# blink1mk3_005t5_5050.net
KiCad netlist of a schematic drawn in EAGLE
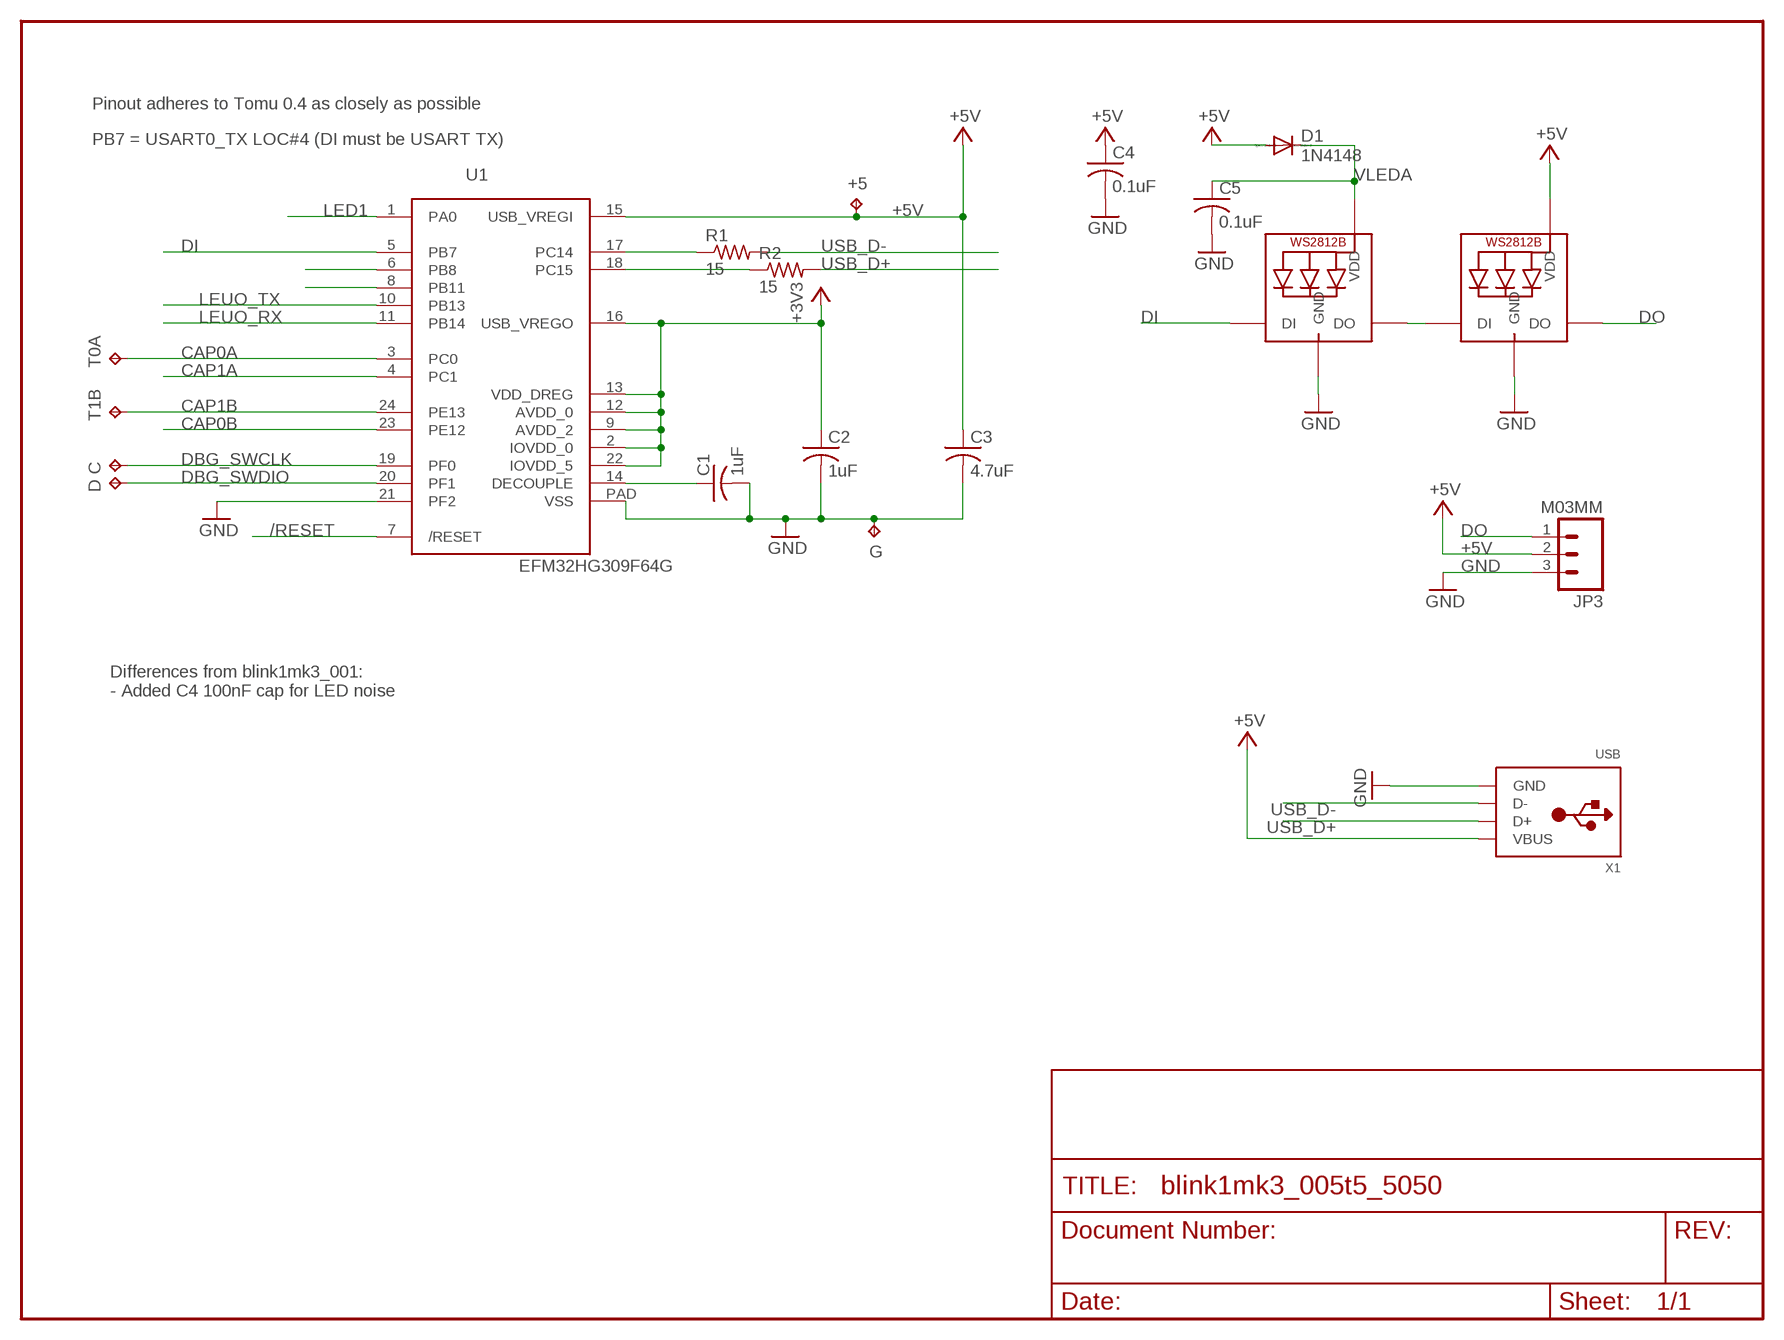
[diagram p0: schematic, sheet 1]

(export (version "E")
  (design (tool "Eeschema 10.0.6"))
  (components
    (comp (ref "+5")
      (value "TPTP10R")
      (footprint "eagle-import:TP10R")
      (libsource (lib "eagle-import") (part "TPTP10R"))
    )
    (comp (ref "C")
      (value "TPTP10R")
      (footprint "eagle-import:TP10R")
      (libsource (lib "eagle-import") (part "TPTP10R"))
    )
    (comp (ref "C1")
      (value "1uF")
      (footprint "eagle-import:C0402")
      (libsource (lib "eagle-import") (part "C-USC0402"))
    )
    (comp (ref "C2")
      (value "1uF")
      (footprint "eagle-import:C0402")
      (libsource (lib "eagle-import") (part "C-USC0402"))
    )
    (comp (ref "C3")
      (value "4.7uF")
      (footprint "eagle-import:C0402")
      (libsource (lib "eagle-import") (part "C-USC0402"))
    )
    (comp (ref "C4")
      (value "0.1uF")
      (footprint "eagle-import:C0402")
      (libsource (lib "eagle-import") (part "C-USC0402"))
    )
    (comp (ref "C5")
      (value "0.1uF")
      (footprint "eagle-import:C0402")
      (libsource (lib "eagle-import") (part "C-USC0402"))
    )
    (comp (ref "D")
      (value "TPTP10R")
      (footprint "eagle-import:TP10R")
      (libsource (lib "eagle-import") (part "TPTP10R"))
    )
    (comp (ref "D1")
      (value "1N4148")
      (footprint "eagle-import:SOD523")
      (libsource (lib "eagle-import") (part "DIODE-SOD523"))
    )
    (comp (ref "G")
      (value "TPTP10R")
      (footprint "eagle-import:TP10R")
      (libsource (lib "eagle-import") (part "TPTP10R"))
    )
    (comp (ref "JP3")
      (value "M03MM")
      (footprint "eagle-import:1X03-1.5MM")
      (libsource (lib "eagle-import") (part "M03MM"))
    )
    (comp (ref "LED1")
      (value "SK6812MINI")
      (footprint "eagle-import:WS2812B")
      (libsource (lib "eagle-import") (part "WS2812B5050"))
    )
    (comp (ref "LED2")
      (value "SK6812MINI")
      (footprint "eagle-import:WS2812B")
      (libsource (lib "eagle-import") (part "WS2812B5050"))
    )
    (comp (ref "R1")
      (value "15")
      (footprint "eagle-import:R0402")
      (libsource (lib "eagle-import") (part "R-US_R0402"))
    )
    (comp (ref "R2")
      (value "15")
      (footprint "eagle-import:R0402")
      (libsource (lib "eagle-import") (part "R-US_R0402"))
    )
    (comp (ref "T0A")
      (value "TPTP15R")
      (footprint "eagle-import:TP15R")
      (libsource (lib "eagle-import") (part "TPTP15R"))
    )
    (comp (ref "T1B")
      (value "TPTP15R")
      (footprint "eagle-import:TP15R")
      (libsource (lib "eagle-import") (part "TPTP15R"))
    )
    (comp (ref "U1")
      (value "EFM32HG309F64G")
      (footprint "eagle-import:QFN24PAD")
      (libsource (lib "eagle-import") (part "EFM32HG309F64G"))
    )
    (comp (ref "X1")
      (value "USB")
      (footprint "eagle-import:MOLEX-48037-1000")
      (libsource (lib "eagle-import") (part "USB"))
    )
  )
  (nets
    (net (code "1") (name "+3V3") (class "Default")
      (node (ref "C2") (pin "1") (pinfunction "1_1") (pintype "passive"))
      (node (ref "U1") (pin "12") (pinfunction "AVDD_0_12") (pintype "bidirectional"))
      (node (ref "U1") (pin "13") (pinfunction "VDD_DREG_13") (pintype "bidirectional"))
      (node (ref "U1") (pin "16") (pinfunction "USB_VREGO_16") (pintype "bidirectional"))
      (node (ref "U1") (pin "2") (pinfunction "IOVDD_0_2") (pintype "bidirectional"))
      (node (ref "U1") (pin "22") (pinfunction "IOVDD_5_22") (pintype "bidirectional"))
      (node (ref "U1") (pin "9") (pinfunction "AVDD_2_9") (pintype "bidirectional"))
    )
    (net (code "2") (name "+5V") (class "Default")
      (node (ref "+5") (pin "TP") (pinfunction "TP_TP") (pintype "input"))
      (node (ref "C3") (pin "1") (pinfunction "1_1") (pintype "passive"))
      (node (ref "C4") (pin "1") (pinfunction "1_1") (pintype "passive"))
      (node (ref "D1") (pin "A") (pinfunction "A_A") (pintype "passive"))
      (node (ref "JP3") (pin "2") (pinfunction "2_2") (pintype "passive"))
      (node (ref "LED2") (pin "1-VDD") (pinfunction "VDD_1-VDD") (pintype "power_in"))
      (node (ref "U1") (pin "15") (pinfunction "USB_VREGI_15") (pintype "bidirectional"))
      (node (ref "X1") (pin "1") (pinfunction "VBUS_1") (pintype "power_in"))
    )
    (net (code "3") (name "/CAP0A") (class "Default")
      (node (ref "T0A") (pin "TP") (pinfunction "TP_TP") (pintype "input"))
      (node (ref "U1") (pin "3") (pinfunction "PC0_3") (pintype "bidirectional"))
    )
    (net (code "4") (name "/CAP0B") (class "Default")
      (node (ref "U1") (pin "23") (pinfunction "PE12_23") (pintype "bidirectional"))
    )
    (net (code "5") (name "/CAP1A") (class "Default")
      (node (ref "U1") (pin "4") (pinfunction "PC1_4") (pintype "bidirectional"))
    )
    (net (code "6") (name "/CAP1B") (class "Default")
      (node (ref "T1B") (pin "TP") (pinfunction "TP_TP") (pintype "input"))
      (node (ref "U1") (pin "24") (pinfunction "PE13_24") (pintype "bidirectional"))
    )
    (net (code "7") (name "/DBG_SWCLK") (class "Default")
      (node (ref "C") (pin "TP") (pinfunction "TP_TP") (pintype "input"))
      (node (ref "U1") (pin "19") (pinfunction "PF0_19") (pintype "bidirectional"))
    )
    (net (code "8") (name "/DBG_SWDIO") (class "Default")
      (node (ref "D") (pin "TP") (pinfunction "TP_TP") (pintype "input"))
      (node (ref "U1") (pin "20") (pinfunction "PF1_20") (pintype "bidirectional"))
    )
    (net (code "9") (name "/DI") (class "Default")
      (node (ref "LED1") (pin "4-DIN") (pinfunction "DI_4-DIN") (pintype "input"))
      (node (ref "U1") (pin "5") (pinfunction "PB7_5") (pintype "bidirectional"))
    )
    (net (code "10") (name "/DO") (class "Default")
      (node (ref "JP3") (pin "1") (pinfunction "1_1") (pintype "passive"))
      (node (ref "LED2") (pin "2-DOUT") (pinfunction "DO_2-DOUT") (pintype "output"))
    )
    (net (code "11") (name "/LED1") (class "Default")
      (node (ref "U1") (pin "1") (pinfunction "PA0_1") (pintype "bidirectional"))
    )
    (net (code "12") (name "/LEUO_RX") (class "Default")
      (node (ref "U1") (pin "11") (pinfunction "PB14_11") (pintype "bidirectional"))
    )
    (net (code "13") (name "/LEUO_TX") (class "Default")
      (node (ref "U1") (pin "10") (pinfunction "PB13_10") (pintype "bidirectional"))
    )
    (net (code "14") (name "/USB_D+") (class "Default")
      (node (ref "R2") (pin "2") (pinfunction "2_2") (pintype "passive"))
      (node (ref "X1") (pin "3") (pinfunction "D+_3") (pintype "bidirectional"))
    )
    (net (code "15") (name "/USB_D-") (class "Default")
      (node (ref "R1") (pin "2") (pinfunction "2_2") (pintype "passive"))
      (node (ref "X1") (pin "2") (pinfunction "D-_2") (pintype "bidirectional"))
    )
    (net (code "16") (name "/VLEDA") (class "Default")
      (node (ref "C5") (pin "1") (pinfunction "1_1") (pintype "passive"))
      (node (ref "D1") (pin "C") (pinfunction "C_C") (pintype "passive"))
      (node (ref "LED1") (pin "1-VDD") (pinfunction "VDD_1-VDD") (pintype "power_in"))
    )
    (net (code "17") (name "/{slash}RESET") (class "Default")
      (node (ref "U1") (pin "7") (pinfunction "/RESET_7") (pintype "bidirectional"))
    )
    (net (code "18") (name "GND") (class "Default")
      (node (ref "C1") (pin "2") (pinfunction "2_2") (pintype "passive"))
      (node (ref "C2") (pin "2") (pinfunction "2_2") (pintype "passive"))
      (node (ref "C3") (pin "2") (pinfunction "2_2") (pintype "passive"))
      (node (ref "C4") (pin "2") (pinfunction "2_2") (pintype "passive"))
      (node (ref "C5") (pin "2") (pinfunction "2_2") (pintype "passive"))
      (node (ref "G") (pin "TP") (pinfunction "TP_TP") (pintype "input"))
      (node (ref "JP3") (pin "3") (pinfunction "3_3") (pintype "passive"))
      (node (ref "LED1") (pin "3-GND") (pinfunction "GND_3-GND") (pintype "power_in"))
      (node (ref "LED2") (pin "3-GND") (pinfunction "GND_3-GND") (pintype "power_in"))
      (node (ref "U1") (pin "21") (pinfunction "PF2_21") (pintype "bidirectional"))
      (node (ref "U1") (pin "PAD") (pinfunction "VSS_PAD") (pintype "bidirectional"))
      (node (ref "X1") (pin "4") (pinfunction "GND_4") (pintype "power_in"))
    )
    (net (code "19") (name "Net-(LED1-DO)") (class "Default")
      (node (ref "LED1") (pin "2-DOUT") (pinfunction "DO_2-DOUT") (pintype "output"))
      (node (ref "LED2") (pin "4-DIN") (pinfunction "DI_4-DIN") (pintype "input"))
    )
    (net (code "20") (name "Net-(U1-DECOUPLE)") (class "Default")
      (node (ref "C1") (pin "1") (pinfunction "1_1") (pintype "passive"))
      (node (ref "U1") (pin "14") (pinfunction "DECOUPLE_14") (pintype "bidirectional"))
    )
    (net (code "21") (name "Net-(U1-PC14)") (class "Default")
      (node (ref "R1") (pin "1") (pinfunction "1_1") (pintype "passive"))
      (node (ref "U1") (pin "17") (pinfunction "PC14_17") (pintype "bidirectional"))
    )
    (net (code "22") (name "Net-(U1-PC15)") (class "Default")
      (node (ref "R2") (pin "1") (pinfunction "1_1") (pintype "passive"))
      (node (ref "U1") (pin "18") (pinfunction "PC15_18") (pintype "bidirectional"))
    )
    (net (code "23") (name "unconnected-(U1-PB8-Pad6)") (class "Default")
      (node (ref "U1") (pin "6") (pinfunction "PB8_6") (pintype "bidirectional"))
    )
    (net (code "24") (name "unconnected-(U1-PB11-Pad8)") (class "Default")
      (node (ref "U1") (pin "8") (pinfunction "PB11_8") (pintype "bidirectional"))
    )
  )
)
